# UKHASnetWifiNode.net
KiCad netlist of a schematic drawn in EAGLE
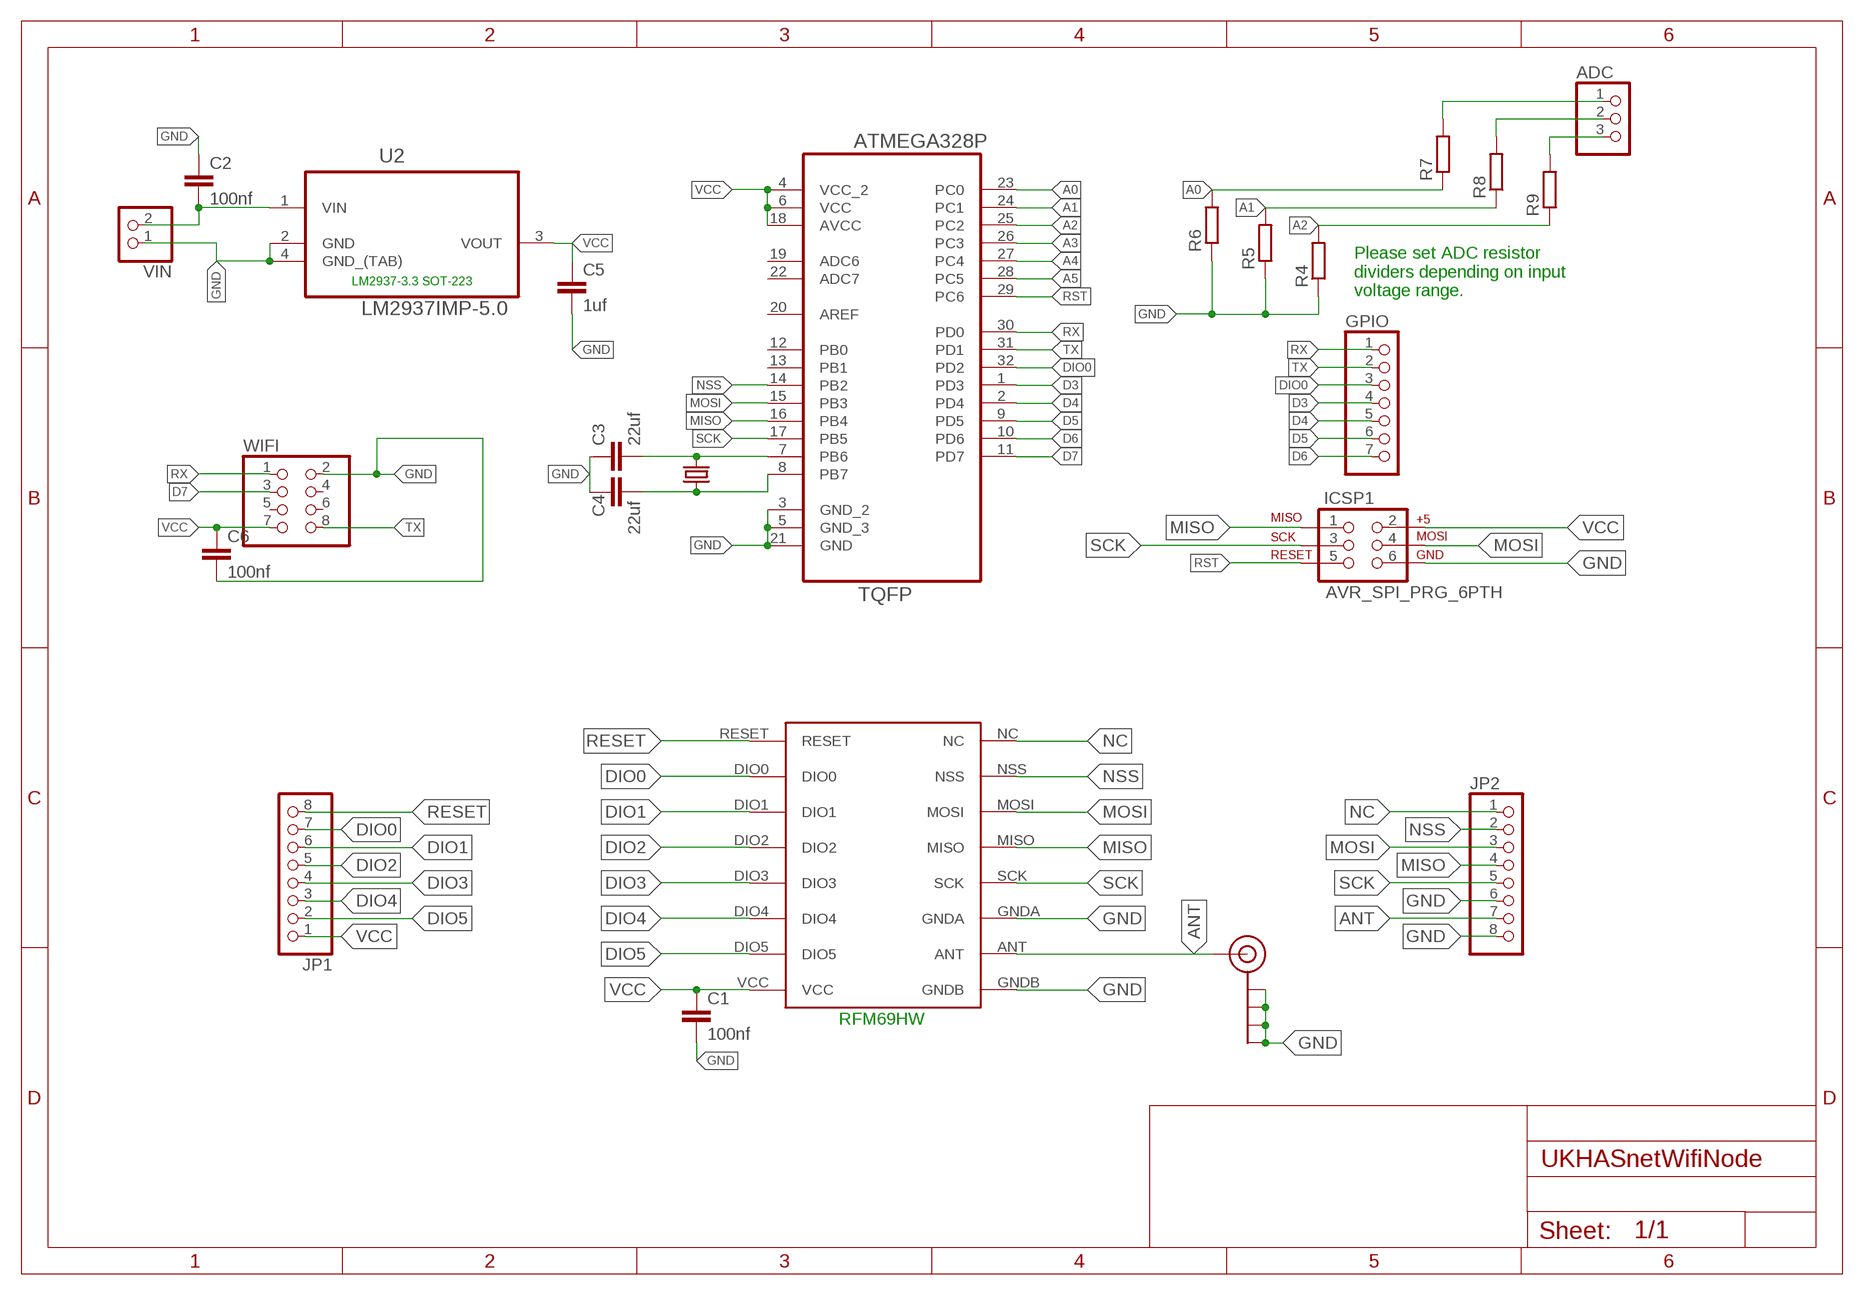
[diagram p0: schematic, sheet 1]

(export (version "E")
  (design (tool "Eeschema 10.0.6"))
  (components
    (comp (ref "ADC")
      (value "PINHD-1X3")
      (footprint "eagle-import:1X03")
      (libsource (lib "eagle-import") (part "PINHD-1X3"))
    )
    (comp (ref "C1")
      (value "100nf")
      (footprint "eagle-import:C0603")
      (libsource (lib "eagle-import") (part "C-EUC0603"))
    )
    (comp (ref "C2")
      (value "100nf")
      (footprint "eagle-import:C0603")
      (libsource (lib "eagle-import") (part "C-EUC0603"))
    )
    (comp (ref "C3")
      (value "22uf")
      (footprint "eagle-import:C0603")
      (libsource (lib "eagle-import") (part "C-EUC0603"))
    )
    (comp (ref "C4")
      (value "22uf")
      (footprint "eagle-import:C0603")
      (libsource (lib "eagle-import") (part "C-EUC0603"))
    )
    (comp (ref "C5")
      (value "1uf")
      (footprint "eagle-import:C0603")
      (libsource (lib "eagle-import") (part "C-EUC0603"))
    )
    (comp (ref "C6")
      (value "100nf")
      (footprint "eagle-import:C0603")
      (libsource (lib "eagle-import") (part "C-EUC0603"))
    )
    (comp (ref "GPIO")
      (value "PINHD-1X7")
      (footprint "eagle-import:1X07")
      (libsource (lib "eagle-import") (part "PINHD-1X7"))
    )
    (comp (ref "ICSP1")
      (value "AVR_SPI_PRG_6PTH")
      (footprint "eagle-import:2X3")
      (libsource (lib "eagle-import") (part "AVR_SPI_PRG_6PTH"))
    )
    (comp (ref "J$1")
      (value "SMA_EDGE")
      (footprint "eagle-import:SMA-EDGE")
      (libsource (lib "eagle-import") (part "SMA_EDGE"))
    )
    (comp (ref "JP1")
      (value "PINHD-1X8")
      (footprint "eagle-import:1X08")
      (libsource (lib "eagle-import") (part "PINHD-1X8"))
    )
    (comp (ref "JP2")
      (value "PINHD-1X8")
      (footprint "eagle-import:1X08")
      (libsource (lib "eagle-import") (part "PINHD-1X8"))
    )
    (comp (ref "R4")
      (value "R-EU_R0603")
      (footprint "eagle-import:R0603")
      (libsource (lib "eagle-import") (part "R-EU_R0603"))
    )
    (comp (ref "R5")
      (value "R-EU_R0603")
      (footprint "eagle-import:R0603")
      (libsource (lib "eagle-import") (part "R-EU_R0603"))
    )
    (comp (ref "R6")
      (value "R-EU_R0603")
      (footprint "eagle-import:R0603")
      (libsource (lib "eagle-import") (part "R-EU_R0603"))
    )
    (comp (ref "R7")
      (value "R-EU_R0603")
      (footprint "eagle-import:R0603")
      (libsource (lib "eagle-import") (part "R-EU_R0603"))
    )
    (comp (ref "R8")
      (value "R-EU_R0603")
      (footprint "eagle-import:R0603")
      (libsource (lib "eagle-import") (part "R-EU_R0603"))
    )
    (comp (ref "R9")
      (value "R-EU_R0603")
      (footprint "eagle-import:R0603")
      (libsource (lib "eagle-import") (part "R-EU_R0603"))
    )
    (comp (ref "U$1")
      (value "RFM69HW")
      (footprint "eagle-import:RFM")
      (libsource (lib "eagle-import") (part "RFM69HW"))
    )
    (comp (ref "U$2")
      (value "8MHz")
      (footprint "eagle-import:ABM03_HC49")
      (libsource (lib "eagle-import") (part "ABRACON_ABM3_CRYSTALABM03_HC49"))
    )
    (comp (ref "U1")
      (value "ATMEGA328P-AU")
      (footprint "eagle-import:QFP80P900X900X120-32N")
      (libsource (lib "eagle-import") (part "ATMEGA328P-AU"))
    )
    (comp (ref "U2")
      (value "LM2937IMP-5.0")
      (footprint "eagle-import:SOT230P700X180-4N")
      (libsource (lib "eagle-import") (part "LM2937IMP-5.0"))
    )
    (comp (ref "VIN")
      (value "PINHD-1X2")
      (footprint "eagle-import:1X02")
      (libsource (lib "eagle-import") (part "PINHD-1X2"))
    )
    (comp (ref "WIFI")
      (value "PINHD-2X4")
      (footprint "eagle-import:2X04")
      (libsource (lib "eagle-import") (part "PINHD-2X4"))
    )
  )
  (nets
    (net (code "1") (name "A0") (class "Default")
      (node (ref "R6") (pin "2") (pinfunction "2_2") (pintype "passive"))
      (node (ref "R7") (pin "1") (pinfunction "1_1") (pintype "passive"))
      (node (ref "U1") (pin "23") (pinfunction "PC0_23") (pintype "bidirectional"))
    )
    (net (code "2") (name "A1") (class "Default")
      (node (ref "R5") (pin "2") (pinfunction "2_2") (pintype "passive"))
      (node (ref "R8") (pin "1") (pinfunction "1_1") (pintype "passive"))
      (node (ref "U1") (pin "24") (pinfunction "PC1_24") (pintype "bidirectional"))
    )
    (net (code "3") (name "A2") (class "Default")
      (node (ref "R4") (pin "2") (pinfunction "2_2") (pintype "passive"))
      (node (ref "R9") (pin "1") (pinfunction "1_1") (pintype "passive"))
      (node (ref "U1") (pin "25") (pinfunction "PC2_25") (pintype "bidirectional"))
    )
    (net (code "4") (name "A3") (class "Default")
      (node (ref "U1") (pin "26") (pinfunction "PC3_26") (pintype "bidirectional"))
    )
    (net (code "5") (name "A4") (class "Default")
      (node (ref "U1") (pin "27") (pinfunction "PC4_27") (pintype "bidirectional"))
    )
    (net (code "6") (name "A5") (class "Default")
      (node (ref "U1") (pin "28") (pinfunction "PC5_28") (pintype "bidirectional"))
    )
    (net (code "7") (name "ANT") (class "Default")
      (node (ref "J$1") (pin "SIG") (pinfunction "SIGNAL_SIG") (pintype "bidirectional"))
      (node (ref "JP2") (pin "7") (pinfunction "7_7") (pintype "passive"))
      (node (ref "U$1") (pin "ANT") (pinfunction "ANT_ANT") (pintype "bidirectional"))
    )
    (net (code "8") (name "D3") (class "Default")
      (node (ref "GPIO") (pin "4") (pinfunction "4_4") (pintype "passive"))
      (node (ref "U1") (pin "1") (pinfunction "PD3_1") (pintype "bidirectional"))
    )
    (net (code "9") (name "D4") (class "Default")
      (node (ref "GPIO") (pin "5") (pinfunction "5_5") (pintype "passive"))
      (node (ref "U1") (pin "2") (pinfunction "PD4_2") (pintype "bidirectional"))
    )
    (net (code "10") (name "D5") (class "Default")
      (node (ref "GPIO") (pin "6") (pinfunction "6_6") (pintype "passive"))
      (node (ref "U1") (pin "9") (pinfunction "PD5_9") (pintype "bidirectional"))
    )
    (net (code "11") (name "D6") (class "Default")
      (node (ref "GPIO") (pin "7") (pinfunction "7_7") (pintype "passive"))
      (node (ref "U1") (pin "10") (pinfunction "PD6_10") (pintype "bidirectional"))
    )
    (net (code "12") (name "D7") (class "Default")
      (node (ref "U1") (pin "11") (pinfunction "PD7_11") (pintype "bidirectional"))
      (node (ref "WIFI") (pin "3") (pinfunction "CH_PD_3") (pintype "passive"))
    )
    (net (code "13") (name "DIO0") (class "Default")
      (node (ref "GPIO") (pin "3") (pinfunction "3_3") (pintype "passive"))
      (node (ref "JP1") (pin "7") (pinfunction "7_7") (pintype "passive"))
      (node (ref "U$1") (pin "DIO0") (pinfunction "DIO0_DIO0") (pintype "bidirectional"))
      (node (ref "U1") (pin "32") (pinfunction "PD2_32") (pintype "bidirectional"))
    )
    (net (code "14") (name "DIO1") (class "Default")
      (node (ref "JP1") (pin "6") (pinfunction "6_6") (pintype "passive"))
      (node (ref "U$1") (pin "DIO1") (pinfunction "DIO1_DIO1") (pintype "bidirectional"))
    )
    (net (code "15") (name "DIO2") (class "Default")
      (node (ref "JP1") (pin "5") (pinfunction "5_5") (pintype "passive"))
      (node (ref "U$1") (pin "DIO2") (pinfunction "DIO2_DIO2") (pintype "bidirectional"))
    )
    (net (code "16") (name "DIO3") (class "Default")
      (node (ref "JP1") (pin "4") (pinfunction "4_4") (pintype "passive"))
      (node (ref "U$1") (pin "DIO3") (pinfunction "DIO3_DIO3") (pintype "bidirectional"))
    )
    (net (code "17") (name "DIO4") (class "Default")
      (node (ref "JP1") (pin "3") (pinfunction "3_3") (pintype "passive"))
      (node (ref "U$1") (pin "DIO4") (pinfunction "DIO4_DIO4") (pintype "bidirectional"))
    )
    (net (code "18") (name "DIO5") (class "Default")
      (node (ref "JP1") (pin "2") (pinfunction "2_2") (pintype "passive"))
      (node (ref "U$1") (pin "DIO5") (pinfunction "DIO5_DIO5") (pintype "bidirectional"))
    )
    (net (code "19") (name "GND") (class "Default")
      (node (ref "C1") (pin "2") (pinfunction "2_2") (pintype "passive"))
      (node (ref "C2") (pin "1") (pinfunction "1_1") (pintype "passive"))
      (node (ref "C3") (pin "1") (pinfunction "1_1") (pintype "passive"))
      (node (ref "C4") (pin "1") (pinfunction "1_1") (pintype "passive"))
      (node (ref "C5") (pin "2") (pinfunction "2_2") (pintype "passive"))
      (node (ref "C6") (pin "2") (pinfunction "2_2") (pintype "passive"))
      (node (ref "ICSP1") (pin "6") (pinfunction "6_6") (pintype "passive"))
      (node (ref "J$1") (pin "GND@0") (pinfunction "GND_GND@0") (pintype "bidirectional"))
      (node (ref "J$1") (pin "GND@1") (pinfunction "GND_GND@1") (pintype "bidirectional"))
      (node (ref "J$1") (pin "GND@2") (pinfunction "GND_GND@2") (pintype "bidirectional"))
      (node (ref "J$1") (pin "GND@3") (pinfunction "GND_GND@3") (pintype "bidirectional"))
      (node (ref "JP2") (pin "6") (pinfunction "6_6") (pintype "passive"))
      (node (ref "JP2") (pin "8") (pinfunction "8_8") (pintype "passive"))
      (node (ref "R4") (pin "1") (pinfunction "1_1") (pintype "passive"))
      (node (ref "R5") (pin "1") (pinfunction "1_1") (pintype "passive"))
      (node (ref "R6") (pin "1") (pinfunction "1_1") (pintype "passive"))
      (node (ref "U$1") (pin "GNDA") (pinfunction "GNDA_GNDA") (pintype "bidirectional"))
      (node (ref "U$1") (pin "GNDB") (pinfunction "GNDB_GNDB") (pintype "bidirectional"))
      (node (ref "U1") (pin "21") (pinfunction "GND_21") (pintype "passive"))
      (node (ref "U1") (pin "3") (pinfunction "GND_2_3") (pintype "passive"))
      (node (ref "U1") (pin "5") (pinfunction "GND_3_5") (pintype "passive"))
      (node (ref "U2") (pin "2") (pinfunction "GND_2") (pintype "passive"))
      (node (ref "U2") (pin "4") (pinfunction "GND_(TAB)_4") (pintype "passive"))
      (node (ref "VIN") (pin "1") (pinfunction "1_1") (pintype "passive"))
      (node (ref "WIFI") (pin "2") (pinfunction "GND_2") (pintype "passive"))
    )
    (net (code "20") (name "MISO") (class "Default")
      (node (ref "ICSP1") (pin "1") (pinfunction "1_1") (pintype "passive"))
      (node (ref "JP2") (pin "4") (pinfunction "4_4") (pintype "passive"))
      (node (ref "U$1") (pin "MISO") (pinfunction "MISO_MISO") (pintype "bidirectional"))
      (node (ref "U1") (pin "16") (pinfunction "PB4_16") (pintype "bidirectional"))
    )
    (net (code "21") (name "MOSI") (class "Default")
      (node (ref "ICSP1") (pin "4") (pinfunction "4_4") (pintype "passive"))
      (node (ref "JP2") (pin "3") (pinfunction "3_3") (pintype "passive"))
      (node (ref "U$1") (pin "MOSI") (pinfunction "MOSI_MOSI") (pintype "bidirectional"))
      (node (ref "U1") (pin "15") (pinfunction "PB3_15") (pintype "bidirectional"))
    )
    (net (code "22") (name "NC") (class "Default")
      (node (ref "JP2") (pin "1") (pinfunction "1_1") (pintype "passive"))
      (node (ref "U$1") (pin "NC") (pinfunction "NC_NC") (pintype "bidirectional"))
    )
    (net (code "23") (name "NSS") (class "Default")
      (node (ref "JP2") (pin "2") (pinfunction "2_2") (pintype "passive"))
      (node (ref "U$1") (pin "NSS") (pinfunction "NSS_NSS") (pintype "bidirectional"))
      (node (ref "U1") (pin "14") (pinfunction "PB2_14") (pintype "bidirectional"))
    )
    (net (code "24") (name "Net-(ADC-Pad1)") (class "Default")
      (node (ref "ADC") (pin "1") (pinfunction "1_1") (pintype "passive"))
      (node (ref "R7") (pin "2") (pinfunction "2_2") (pintype "passive"))
    )
    (net (code "25") (name "Net-(ADC-Pad2)") (class "Default")
      (node (ref "ADC") (pin "2") (pinfunction "2_2") (pintype "passive"))
      (node (ref "R8") (pin "2") (pinfunction "2_2") (pintype "passive"))
    )
    (net (code "26") (name "Net-(ADC-Pad3)") (class "Default")
      (node (ref "ADC") (pin "3") (pinfunction "3_3") (pintype "passive"))
      (node (ref "R9") (pin "2") (pinfunction "2_2") (pintype "passive"))
    )
    (net (code "27") (name "Net-(U1-PB6)") (class "Default")
      (node (ref "C3") (pin "2") (pinfunction "2_2") (pintype "passive"))
      (node (ref "U$2") (pin "2") (pinfunction "2_2") (pintype "passive"))
      (node (ref "U1") (pin "7") (pinfunction "PB6_7") (pintype "bidirectional"))
    )
    (net (code "28") (name "Net-(U1-PB7)") (class "Default")
      (node (ref "C4") (pin "2") (pinfunction "2_2") (pintype "passive"))
      (node (ref "U$2") (pin "1") (pinfunction "1_1") (pintype "passive"))
      (node (ref "U1") (pin "8") (pinfunction "PB7_8") (pintype "bidirectional"))
    )
    (net (code "29") (name "Net-(U2-VIN)") (class "Default")
      (node (ref "C2") (pin "2") (pinfunction "2_2") (pintype "passive"))
      (node (ref "U2") (pin "1") (pinfunction "VIN_1") (pintype "input"))
      (node (ref "VIN") (pin "2") (pinfunction "2_2") (pintype "passive"))
    )
    (net (code "30") (name "RESET") (class "Default")
      (node (ref "JP1") (pin "8") (pinfunction "8_8") (pintype "passive"))
      (node (ref "U$1") (pin "RESET") (pinfunction "RESET_RESET") (pintype "bidirectional"))
    )
    (net (code "31") (name "RST") (class "Default")
      (node (ref "ICSP1") (pin "5") (pinfunction "5_5") (pintype "passive"))
      (node (ref "U1") (pin "29") (pinfunction "PC6_29") (pintype "bidirectional"))
    )
    (net (code "32") (name "RX") (class "Default")
      (node (ref "GPIO") (pin "1") (pinfunction "1_1") (pintype "passive"))
      (node (ref "U1") (pin "30") (pinfunction "PD0_30") (pintype "bidirectional"))
      (node (ref "WIFI") (pin "1") (pinfunction "TXD_1") (pintype "passive"))
    )
    (net (code "33") (name "SCK") (class "Default")
      (node (ref "ICSP1") (pin "3") (pinfunction "3_3") (pintype "passive"))
      (node (ref "JP2") (pin "5") (pinfunction "5_5") (pintype "passive"))
      (node (ref "U$1") (pin "SCK") (pinfunction "SCK_SCK") (pintype "bidirectional"))
      (node (ref "U1") (pin "17") (pinfunction "PB5_17") (pintype "bidirectional"))
    )
    (net (code "34") (name "TX") (class "Default")
      (node (ref "GPIO") (pin "2") (pinfunction "2_2") (pintype "passive"))
      (node (ref "U1") (pin "31") (pinfunction "PD1_31") (pintype "bidirectional"))
      (node (ref "WIFI") (pin "8") (pinfunction "RXD_8") (pintype "passive"))
    )
    (net (code "35") (name "VCC") (class "Default")
      (node (ref "C1") (pin "1") (pinfunction "1_1") (pintype "passive"))
      (node (ref "C5") (pin "1") (pinfunction "1_1") (pintype "passive"))
      (node (ref "C6") (pin "1") (pinfunction "1_1") (pintype "passive"))
      (node (ref "ICSP1") (pin "2") (pinfunction "2_2") (pintype "passive"))
      (node (ref "JP1") (pin "1") (pinfunction "1_1") (pintype "passive"))
      (node (ref "U$1") (pin "VCC") (pinfunction "VCC_VCC") (pintype "bidirectional"))
      (node (ref "U1") (pin "18") (pinfunction "AVCC_18") (pintype "power_in"))
      (node (ref "U1") (pin "4") (pinfunction "VCC_2_4") (pintype "power_in"))
      (node (ref "U1") (pin "6") (pinfunction "VCC_6") (pintype "power_in"))
      (node (ref "U2") (pin "3") (pinfunction "VOUT_3") (pintype "output"))
      (node (ref "WIFI") (pin "7") (pinfunction "VCC_7") (pintype "passive"))
    )
    (net (code "36") (name "unconnected-(U1-ADC6-Pad19)") (class "Default")
      (node (ref "U1") (pin "19") (pinfunction "ADC6_19") (pintype "input"))
    )
    (net (code "37") (name "unconnected-(U1-ADC7-Pad22)") (class "Default")
      (node (ref "U1") (pin "22") (pinfunction "ADC7_22") (pintype "input"))
    )
    (net (code "38") (name "unconnected-(U1-AREF-Pad20)") (class "Default")
      (node (ref "U1") (pin "20") (pinfunction "AREF_20") (pintype "input"))
    )
    (net (code "39") (name "unconnected-(U1-PB0-Pad12)") (class "Default")
      (node (ref "U1") (pin "12") (pinfunction "PB0_12") (pintype "bidirectional"))
    )
    (net (code "40") (name "unconnected-(U1-PB1-Pad13)") (class "Default")
      (node (ref "U1") (pin "13") (pinfunction "PB1_13") (pintype "bidirectional"))
    )
    (net (code "41") (name "unconnected-(WIFI-GPIO0-Pad6)") (class "Default")
      (node (ref "WIFI") (pin "6") (pinfunction "GPIO0_6") (pintype "passive"))
    )
    (net (code "42") (name "unconnected-(WIFI-GPIO2-Pad4)") (class "Default")
      (node (ref "WIFI") (pin "4") (pinfunction "GPIO2_4") (pintype "passive"))
    )
    (net (code "43") (name "unconnected-(WIFI-GPIO16-Pad5)") (class "Default")
      (node (ref "WIFI") (pin "5") (pinfunction "GPIO16_5") (pintype "passive"))
    )
  )
)
